# P03-DAC_OUTPUT.net
KiCad netlist of a schematic drawn in Altium Designer
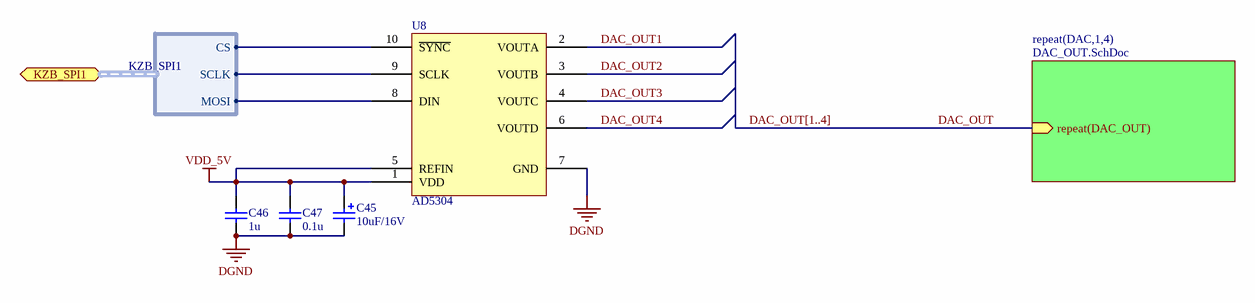
[diagram p0: P03-DAC_OUTPUT.SchDoc]

(export (version "E")
  (design (tool "Eeschema 10.0.6"))
  (components
    (comp (ref "C45")
      (value "10uF/16V")
      (footprint "CAPPLO3_A_3216-18")
      (description "极性电容（表贴）")
      (libsource (lib "MyAD_Library") (part "Cap Pol3"))
    )
    (comp (ref "C46")
      (value "1u")
      (footprint "Cap0603")
      (description "无极性电容（表贴）")
      (libsource (lib "MyAD_Library") (part "Cap Semi"))
    )
    (comp (ref "C47")
      (value "0.1u")
      (footprint "MyAD_Library:Cap0603")
      (description "无极性电容（表贴）")
      (libsource (lib "MyAD_Library") (part "Cap Semi"))
    )
    (comp (ref "U8") (value "AD5304") (footprint "MSOP10") (libsource (lib "Schlib1") (part "AD5304")))
  )
  (nets
    (net (code "2") (name "/CS") (class "Default")
      (node (ref "U8") (pin "10") (pinfunction "~{SYNC}_10") (pintype "passive"))
    )
    (net (code "4") (name "/DAC_OUT1") (class "Default")
      (node (ref "U8") (pin "2") (pinfunction "VOUTA_2") (pintype "passive"))
    )
    (net (code "5") (name "/DAC_OUT2") (class "Default")
      (node (ref "U8") (pin "3") (pinfunction "VOUTB_3") (pintype "passive"))
    )
    (net (code "6") (name "/DAC_OUT3") (class "Default")
      (node (ref "U8") (pin "4") (pinfunction "VOUTC_4") (pintype "passive"))
    )
    (net (code "7") (name "/DAC_OUT4") (class "Default")
      (node (ref "U8") (pin "6") (pinfunction "VOUTD_6") (pintype "passive"))
    )
    (net (code "9") (name "/MOSI") (class "Default")
      (node (ref "U8") (pin "8") (pinfunction "DIN_8") (pintype "passive"))
    )
    (net (code "10") (name "/SCLK") (class "Default")
      (node (ref "U8") (pin "9") (pinfunction "SCLK_9") (pintype "passive"))
    )
    (net (code "12") (name "DGND") (class "Default")
      (node (ref "C45") (pin "2") (pinfunction "2_2") (pintype "passive"))
      (node (ref "C46") (pin "1") (pinfunction "1_1") (pintype "passive"))
      (node (ref "C47") (pin "1") (pinfunction "1_1") (pintype "passive"))
      (node (ref "U8") (pin "7") (pinfunction "GND_7") (pintype "passive"))
    )
    (net (code "13") (name "VDD_5V") (class "Default")
      (node (ref "C45") (pin "1") (pinfunction "1_1") (pintype "passive"))
      (node (ref "C46") (pin "2") (pinfunction "2_2") (pintype "passive"))
      (node (ref "C47") (pin "2") (pinfunction "2_2") (pintype "passive"))
      (node (ref "U8") (pin "1") (pinfunction "VDD_1") (pintype "passive"))
      (node (ref "U8") (pin "5") (pinfunction "REFIN_5") (pintype "passive"))
    )
  )
)
